# Batmngt.net
KiCad netlist of a schematic drawn in Altium Designer
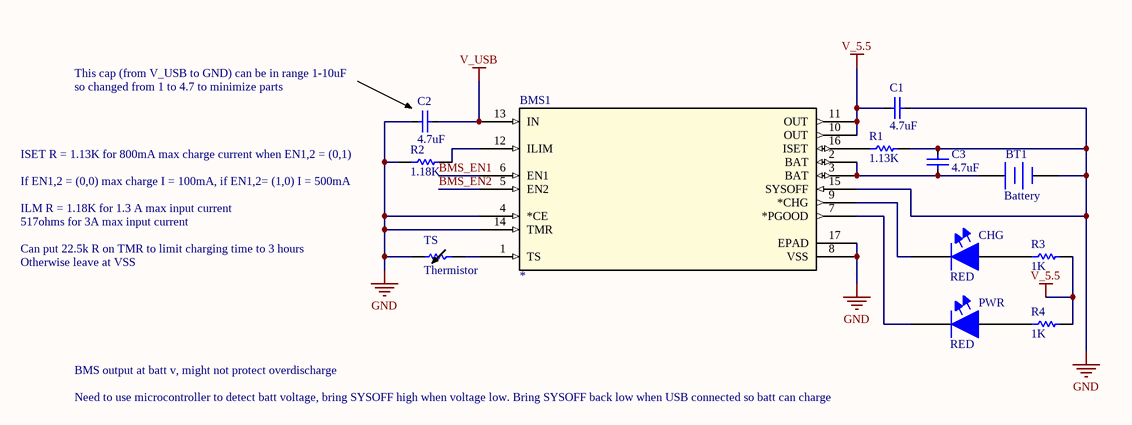
[diagram p0: Batmngt.SchDoc]

(export (version "E")
  (design (tool "Eeschema 10.0.6"))
  (components
    (comp (ref "BMS1")
      (value "*")
      (footprint "RGT16_1P7X1P7")
      (description "Imported")
      (fields
        (field (name "MANUFACTURER") "Texas Instruments")
        (field (name "MANUFACTURER_PART_NUMBER") "BQ24079RGTR")
      )
      (libsource (lib "SuperBot_Schlib1") (part "BQ24079RGTR"))
    )
    (comp (ref "BT1")
      (value "Battery")
      (footprint "BAT-2")
      (description "Multicell Battery")
      (fields (field (name "PUBLISHER") "Altium Limited"))
      (libsource (lib "Miscellaneous Devices") (part "Battery"))
    )
    (comp (ref "C1")
      (value "4.7uF")
      (footprint "CAP0603R")
      (description "Capacitor")
      (fields
        (field (name "MANUFACTURER") "Microchip Technology")
        (field (name "MANUFACTURER PART NUM") "MIC5378YC5-TR")
      )
      (libsource (lib "SuperBot_Schlib1") (part "C"))
    )
    (comp (ref "C2")
      (value "4.7uF")
      (footprint "CAP0603R")
      (description "Capacitor")
      (fields
        (field (name "MANUFACTURER") "Microchip Technology")
        (field (name "MANUFACTURER PART NUM") "MIC5378YC5-TR")
      )
      (libsource (lib "SuperBot_Schlib1") (part "C"))
    )
    (comp (ref "C3")
      (value "4.7uF")
      (footprint "CAP0603R")
      (description "Capacitor")
      (fields
        (field (name "MANUFACTURER") "Microchip Technology")
        (field (name "MANUFACTURER PART NUM") "MIC5378YC5-TR")
      )
      (libsource (lib "SuperBot_Schlib1") (part "C"))
    )
    (comp (ref "CHG")
      (value "RED")
      (footprint "0603_LED")
      (description "LED")
      (libsource (lib "SuperBot_Schlib1") (part "LED"))
    )
    (comp (ref "PWR")
      (value "RED")
      (footprint "0603_LED")
      (description "LED")
      (libsource (lib "SuperBot_Schlib1") (part "LED"))
    )
    (comp (ref "R1")
      (value "1.13K")
      (footprint "RES0603R")
      (description "Resistor")
      (libsource (lib "SuperBot_Schlib1") (part "R"))
    )
    (comp (ref "R2")
      (value "1.18K")
      (footprint "RES0603R")
      (description "Resistor")
      (libsource (lib "SuperBot_Schlib1") (part "R"))
    )
    (comp (ref "R3")
      (value "1K")
      (footprint "RES0603R")
      (description "Resistor")
      (libsource (lib "SuperBot_Schlib1") (part "R"))
    )
    (comp (ref "R4")
      (value "1K")
      (footprint "RES0603R")
      (description "Resistor")
      (libsource (lib "SuperBot_Schlib1") (part "R"))
    )
    (comp (ref "TS")
      (value "Thermistor")
      (footprint "RES0603R")
      (libsource (lib "SuperBot_Schlib1") (part "Thermistor"))
    )
  )
  (nets
    (net (code "1") (name "/BMS_EN1") (class "Default")
      (node (ref "BMS1") (pin "6") (pinfunction "EN1_6") (pintype "input"))
    )
    (net (code "2") (name "/BMS_EN2") (class "Default")
      (node (ref "BMS1") (pin "5") (pinfunction "EN2_5") (pintype "input"))
    )
    (net (code "3") (name "GND") (class "Default")
      (node (ref "BMS1") (pin "14") (pinfunction "TMR_14") (pintype "input"))
      (node (ref "BMS1") (pin "15") (pinfunction "SYSOFF_15") (pintype "input"))
      (node (ref "BMS1") (pin "17") (pinfunction "EPAD_17") (pintype "power_in"))
      (node (ref "BMS1") (pin "4") (pinfunction "*CE_4") (pintype "input"))
      (node (ref "BMS1") (pin "8") (pinfunction "VSS_8") (pintype "power_in"))
      (node (ref "BT1") (pin "2") (pinfunction "-_2") (pintype "passive"))
      (node (ref "C1") (pin "2") (pinfunction "2_2") (pintype "passive"))
      (node (ref "C2") (pin "1") (pinfunction "1_1") (pintype "passive"))
      (node (ref "C3") (pin "1") (pinfunction "1_1") (pintype "passive"))
      (node (ref "R1") (pin "2") (pintype "passive"))
      (node (ref "R2") (pin "1") (pintype "passive"))
      (node (ref "TS") (pin "2") (pintype "passive"))
    )
    (net (code "4") (name "Net-(BMS1-*CHG)") (class "Default")
      (node (ref "BMS1") (pin "9") (pinfunction "*CHG_9") (pintype "output"))
      (node (ref "CHG") (pin "K") (pinfunction "CATHODE_K") (pintype "passive"))
    )
    (net (code "5") (name "Net-(BMS1-*PGOOD)") (class "Default")
      (node (ref "BMS1") (pin "7") (pinfunction "*PGOOD_7") (pintype "output"))
      (node (ref "PWR") (pin "K") (pinfunction "CATHODE_K") (pintype "passive"))
    )
    (net (code "6") (name "Net-(BMS1-ILIM)") (class "Default")
      (node (ref "BMS1") (pin "12") (pinfunction "ILIM_12") (pintype "input"))
      (node (ref "R2") (pin "2") (pintype "passive"))
    )
    (net (code "7") (name "Net-(BMS1-ISET)") (class "Default")
      (node (ref "BMS1") (pin "16") (pinfunction "ISET_16") (pintype "bidirectional"))
      (node (ref "R1") (pin "1") (pintype "passive"))
    )
    (net (code "8") (name "Net-(BMS1-TS)") (class "Default")
      (node (ref "BMS1") (pin "1") (pinfunction "TS_1") (pintype "input"))
      (node (ref "TS") (pin "1") (pintype "passive"))
    )
    (net (code "9") (name "Net-(BT1-+)") (class "Default")
      (node (ref "BMS1") (pin "2") (pinfunction "BAT_2") (pintype "bidirectional"))
      (node (ref "BMS1") (pin "3") (pinfunction "BAT_3") (pintype "bidirectional"))
      (node (ref "BT1") (pin "1") (pinfunction "+_1") (pintype "passive"))
      (node (ref "C3") (pin "2") (pinfunction "2_2") (pintype "passive"))
    )
    (net (code "10") (name "Net-(CHG-ANODE)") (class "Default")
      (node (ref "CHG") (pin "A") (pinfunction "ANODE_A") (pintype "passive"))
      (node (ref "R3") (pin "1") (pintype "passive"))
    )
    (net (code "11") (name "Net-(PWR-ANODE)") (class "Default")
      (node (ref "PWR") (pin "A") (pinfunction "ANODE_A") (pintype "passive"))
      (node (ref "R4") (pin "1") (pintype "passive"))
    )
    (net (code "12") (name "V_5.5") (class "Default")
      (node (ref "BMS1") (pin "10") (pinfunction "OUT_10") (pintype "output"))
      (node (ref "BMS1") (pin "11") (pinfunction "OUT_11") (pintype "output"))
      (node (ref "C1") (pin "1") (pinfunction "1_1") (pintype "passive"))
      (node (ref "R3") (pin "2") (pintype "passive"))
      (node (ref "R4") (pin "2") (pintype "passive"))
    )
    (net (code "13") (name "V_USB") (class "Default")
      (node (ref "BMS1") (pin "13") (pinfunction "IN_13") (pintype "input"))
      (node (ref "C2") (pin "2") (pinfunction "2_2") (pintype "passive"))
    )
  )
)
